# Processor.net
KiCad netlist of a schematic drawn in Altium Designer
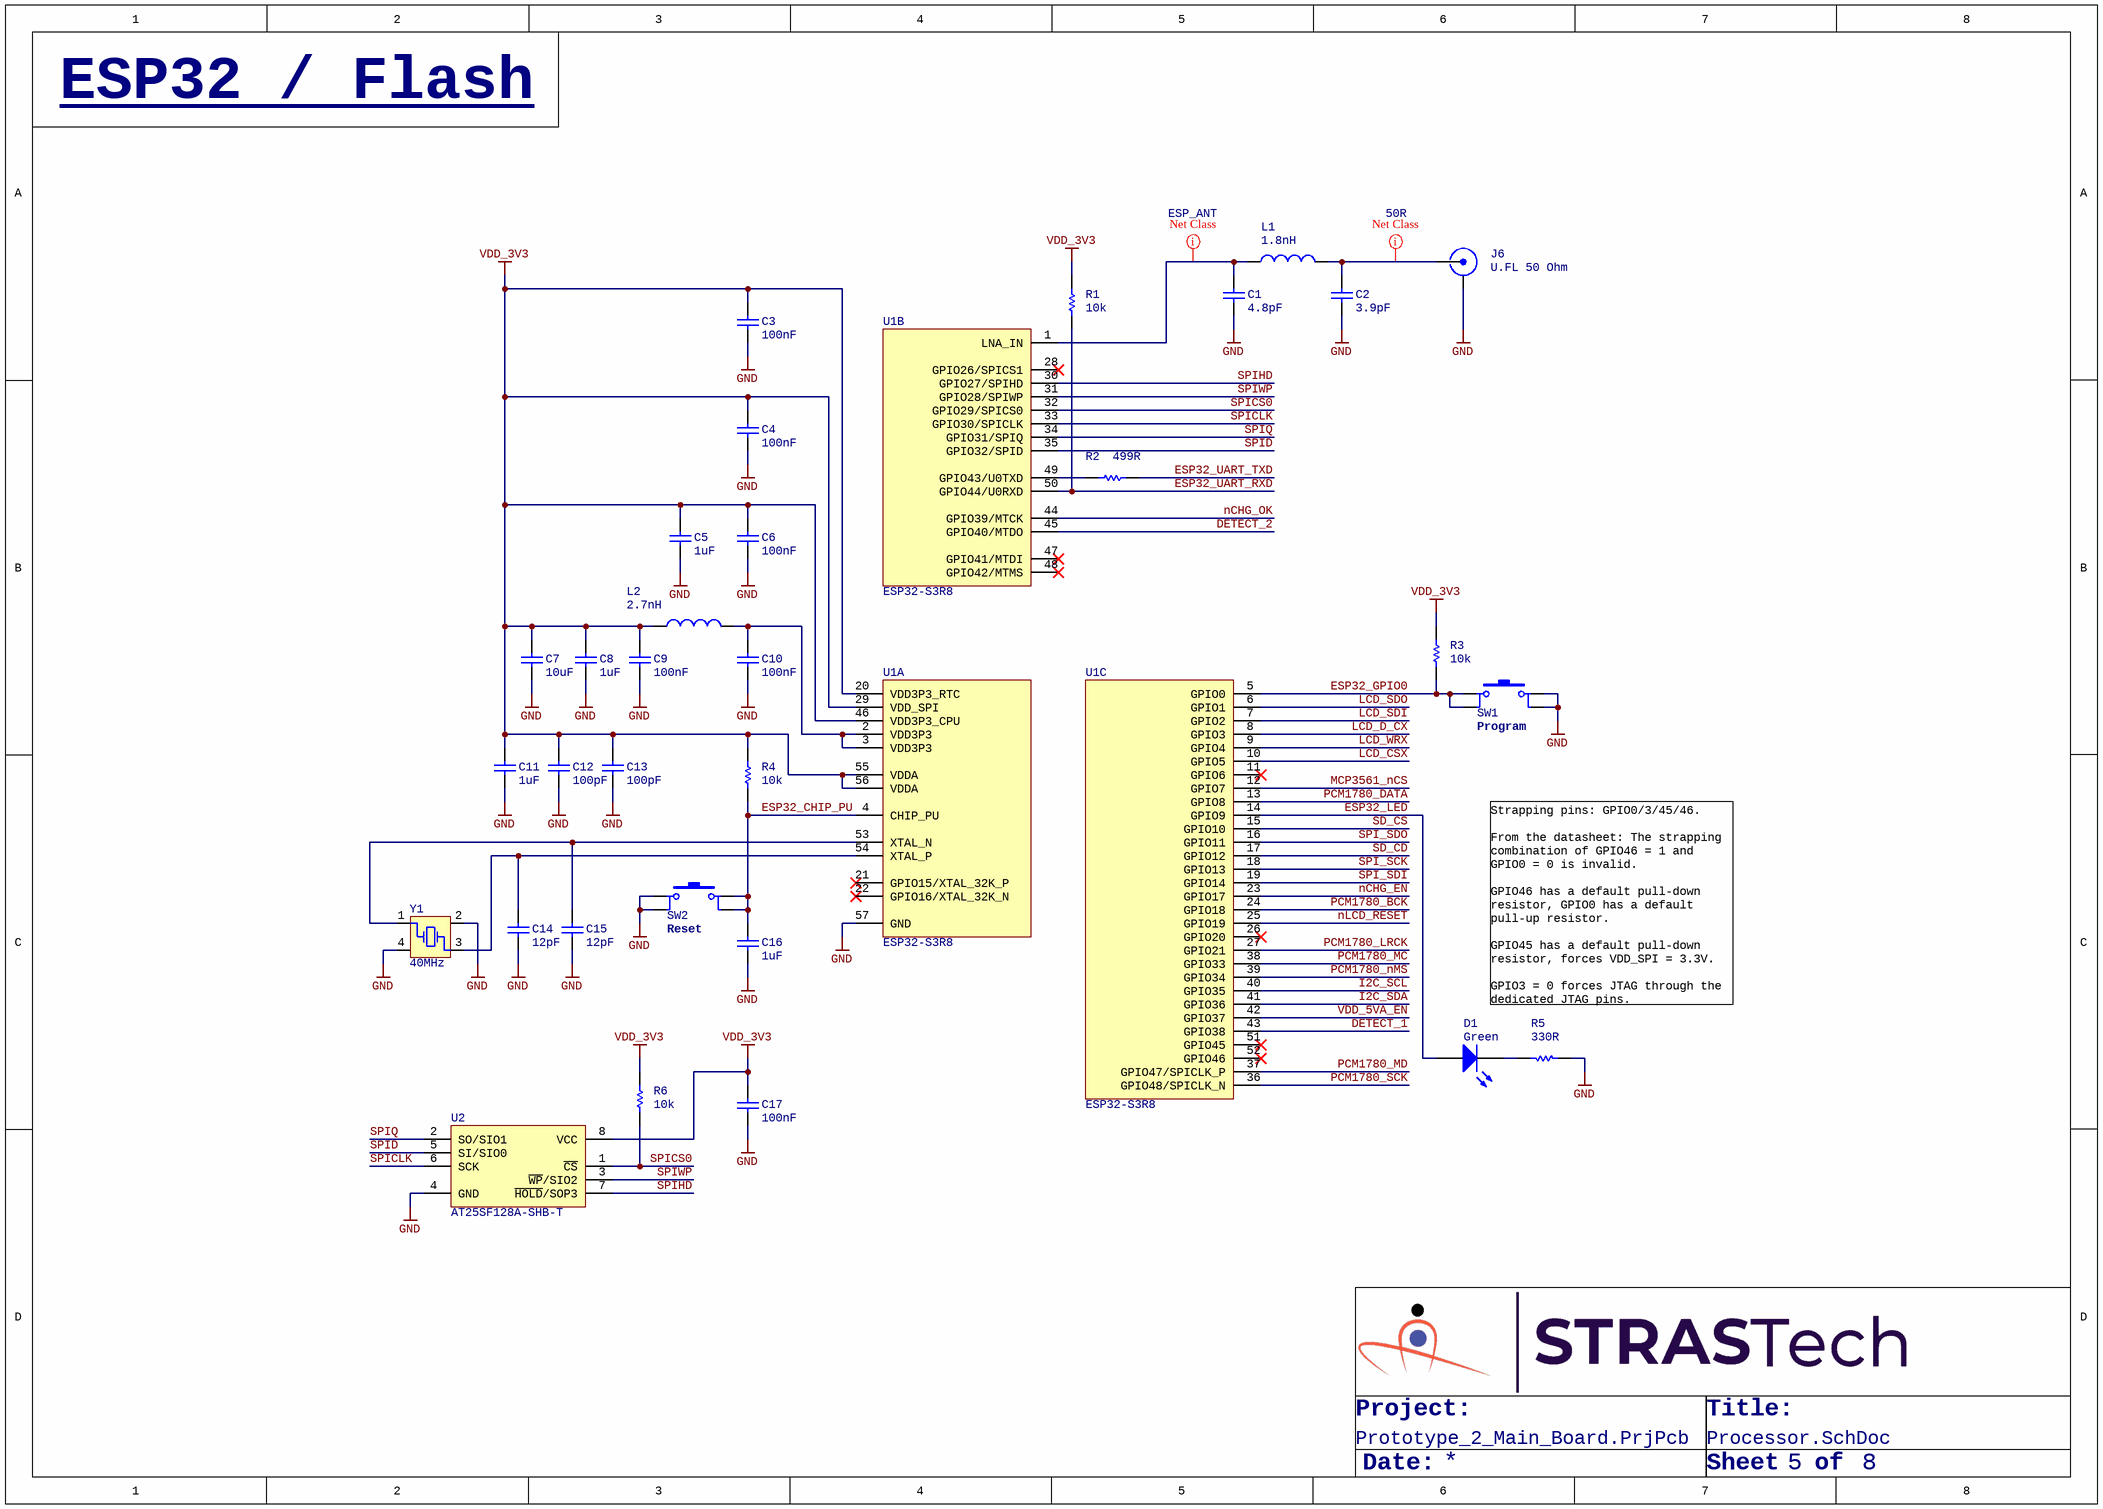
[diagram p0: Processor.SchDoc]

(export (version "E")
  (design (tool "Eeschema 10.0.6"))
  (components
    (comp (ref "C1")
      (value "4.8pF")
      (footprint "Cap,SMD,0402")
      (description "4.8 pF ±0.25pF 50V Ceramic Capacitor C0G, NP0 0402 (1005 Metric)")
      (fields
        (field (name "VENDOR PART NUMBER") "490-17481-1-ND")
        (field (name "MANUFACTURER") "Murata Electronics")
        (field (name "CREATEDBY") "Judd Foster")
      )
      (libsource (lib "symbols") (part "CAP,Cer,4.8pF,50VDC,C0G/NP0,0402"))
    )
    (comp (ref "C2")
      (value "3.9pF")
      (footprint "Cap,SMD,0402")
      (description "3.9 pF ±0.1pF 50V Ceramic Capacitor C0G, NP0 0402 (1005 Metric)")
      (fields
        (field (name "VENDOR PART NUMBER") "399-CBR04C399B5GACCT-ND")
        (field (name "MANUFACTURER") "KEMET")
        (field (name "CREATEDBY") "Judd Foster")
      )
      (libsource (lib "symbols") (part "CAP,Cer,3.9pF,50VDC,C0G/NP0,0402"))
    )
    (comp (ref "C3")
      (value "100nF")
      (footprint "Cap,SMD,0402")
      (description "0.1µF ±10% 25V Ceramic Capacitor X7R 0402 (1005 Metric)")
      (fields
        (field (name "VENDOR PART NUMBER") "490-14603-1-ND")
        (field (name "MANUFACTURER") "Murata Electronics")
        (field (name "CREATEDBY") "Judd Foster")
      )
      (libsource (lib "symbols") (part "CAP,Cer,100nF,25VDC,X7R,0402"))
    )
    (comp (ref "C4")
      (value "100nF")
      (footprint "Cap,SMD,0402")
      (description "0.1µF ±10% 25V Ceramic Capacitor X7R 0402 (1005 Metric)")
      (fields
        (field (name "VENDOR PART NUMBER") "490-14603-1-ND")
        (field (name "MANUFACTURER") "Murata Electronics")
        (field (name "CREATEDBY") "Judd Foster")
      )
      (libsource (lib "symbols") (part "CAP,Cer,100nF,25VDC,X7R,0402"))
    )
    (comp (ref "C5")
      (value "1uF")
      (footprint "Cap,SMD,0402")
      (description "1 µF ±10% 35V Ceramic Capacitor X5R 0402 (1005 Metric)")
      (fields
        (field (name "VENDOR PART NUMBER") "445-9073-1-ND")
        (field (name "MANUFACTURER") "TDK Corporation")
        (field (name "CREATEDBY") "Judd Foster")
      )
      (libsource (lib "symbols") (part "CAP,Cer,1uF,35VDC,X5R,0402"))
    )
    (comp (ref "C6")
      (value "100nF")
      (footprint "Cap,SMD,0402")
      (description "0.1µF ±10% 25V Ceramic Capacitor X7R 0402 (1005 Metric)")
      (fields
        (field (name "VENDOR PART NUMBER") "490-14603-1-ND")
        (field (name "MANUFACTURER") "Murata Electronics")
        (field (name "CREATEDBY") "Judd Foster")
      )
      (libsource (lib "symbols") (part "CAP,Cer,100nF,25VDC,X7R,0402"))
    )
    (comp (ref "C7")
      (value "10uF")
      (footprint "Cap,SMD,0402")
      (description "10 µF ±20% 10V Ceramic Capacitor X5R 0402 (1005 Metric)")
      (fields
        (field (name "VENDOR PART NUMBER") "1276-1450-1-ND")
        (field (name "MANUFACTURER") "Samsung Electro-Mechanics")
        (field (name "CREATEDBY") "Judd Foster")
      )
      (libsource (lib "symbols") (part "CAP,Cer,10uF,10VDC,X5R,0402"))
    )
    (comp (ref "C8")
      (value "1uF")
      (footprint "Cap,SMD,0402")
      (description "1 µF ±10% 35V Ceramic Capacitor X5R 0402 (1005 Metric)")
      (fields
        (field (name "VENDOR PART NUMBER") "445-9073-1-ND")
        (field (name "MANUFACTURER") "TDK Corporation")
        (field (name "CREATEDBY") "Judd Foster")
      )
      (libsource (lib "symbols") (part "CAP,Cer,1uF,35VDC,X5R,0402"))
    )
    (comp (ref "C9")
      (value "100nF")
      (footprint "Cap,SMD,0402")
      (description "0.1µF ±10% 25V Ceramic Capacitor X7R 0402 (1005 Metric)")
      (fields
        (field (name "VENDOR PART NUMBER") "490-14603-1-ND")
        (field (name "MANUFACTURER") "Murata Electronics")
        (field (name "CREATEDBY") "Judd Foster")
      )
      (libsource (lib "symbols") (part "CAP,Cer,100nF,25VDC,X7R,0402"))
    )
    (comp (ref "C10")
      (value "100nF")
      (footprint "Cap,SMD,0402")
      (description "0.1µF ±10% 25V Ceramic Capacitor X7R 0402 (1005 Metric)")
      (fields
        (field (name "VENDOR PART NUMBER") "490-14603-1-ND")
        (field (name "MANUFACTURER") "Murata Electronics")
        (field (name "CREATEDBY") "Judd Foster")
      )
      (libsource (lib "symbols") (part "CAP,Cer,100nF,25VDC,X7R,0402"))
    )
    (comp (ref "C11")
      (value "1uF")
      (footprint "Cap,SMD,0402")
      (description "1 µF ±10% 35V Ceramic Capacitor X5R 0402 (1005 Metric)")
      (fields
        (field (name "VENDOR PART NUMBER") "445-9073-1-ND")
        (field (name "MANUFACTURER") "TDK Corporation")
        (field (name "CREATEDBY") "Judd Foster")
      )
      (libsource (lib "symbols") (part "CAP,Cer,1uF,35VDC,X5R,0402"))
    )
    (comp (ref "C12")
      (value "100pF")
      (footprint "Cap,SMD,0402")
      (description "100pF ±5% 50V Ceramic Capacitor C0G, NP0 0402 (1005 Metric)")
      (fields
        (field (name "VENDOR PART NUMBER") "490-10669-1-ND")
        (field (name "MANUFACTURER") "Murata Electronics")
        (field (name "CREATEDBY") "Judd Foster")
      )
      (libsource (lib "symbols") (part "CAP,Cer,100pF,50VDC,C0G/NP0,0402"))
    )
    (comp (ref "C13")
      (value "100pF")
      (footprint "Cap,SMD,0402")
      (description "100pF ±5% 50V Ceramic Capacitor C0G, NP0 0402 (1005 Metric)")
      (fields
        (field (name "VENDOR PART NUMBER") "490-10669-1-ND")
        (field (name "MANUFACTURER") "Murata Electronics")
        (field (name "CREATEDBY") "Judd Foster")
      )
      (libsource (lib "symbols") (part "CAP,Cer,100pF,50VDC,C0G/NP0,0402"))
    )
    (comp (ref "C14")
      (value "12pF")
      (footprint "Cap,SMD,0402")
      (description "12pF ±5% 50V Ceramic Capacitor C0G, NP0 0402 (1005 Metric)")
      (fields
        (field (name "VENDOR PART NUMBER") "311-1016-1-ND")
        (field (name "MANUFACTURER") "Yageo")
        (field (name "CREATEDBY") "Judd Foster")
      )
      (libsource (lib "symbols") (part "CAP,Cer,12pF,50VDC,C0G/NP0,0402"))
    )
    (comp (ref "C15")
      (value "12pF")
      (footprint "Cap,SMD,0402")
      (description "12pF ±5% 50V Ceramic Capacitor C0G, NP0 0402 (1005 Metric)")
      (fields
        (field (name "VENDOR PART NUMBER") "311-1016-1-ND")
        (field (name "MANUFACTURER") "Yageo")
        (field (name "CREATEDBY") "Judd Foster")
      )
      (libsource (lib "symbols") (part "CAP,Cer,12pF,50VDC,C0G/NP0,0402"))
    )
    (comp (ref "C16")
      (value "1uF")
      (footprint "Cap,SMD,0402")
      (description "1µF ±20% 6.3V Ceramic Capacitor X5R 0402 (1005 Metric)")
      (fields
        (field (name "VENDOR PART NUMBER") "1276-1235-1-ND")
        (field (name "MANUFACTURER") "Samsung Electro-Mechanics")
        (field (name "CREATEDBY") "Judd Foster")
      )
      (libsource (lib "symbols") (part "CAP,Cer,1uF,6.3VDC,X5R,0402"))
    )
    (comp (ref "C17")
      (value "100nF")
      (footprint "Cap,SMD,0402")
      (description "0.1µF ±10% 25V Ceramic Capacitor X7R 0402 (1005 Metric)")
      (fields
        (field (name "VENDOR PART NUMBER") "490-14603-1-ND")
        (field (name "MANUFACTURER") "Murata Electronics")
        (field (name "CREATEDBY") "Judd Foster")
      )
      (libsource (lib "symbols") (part "CAP,Cer,100nF,25VDC,X7R,0402"))
    )
    (comp (ref "D1")
      (value "Green")
      (footprint "LED,0603")
      (description "Green 530nm LED Indication - Discrete 3V 0603 (1608 Metric)")
      (fields
        (field (name "MANUFACTURER") "Stanley Electric Co")
        (field (name "MANUFACTURER PART NUMBER") "THG1111C-0005-TR")
        (field (name "CREATEDBY") "Judd Foster")
      )
      (libsource (lib "symbols") (part "LED,Green,SMD,0603"))
    )
    (comp (ref "J6")
      (value "U.FL 50 Ohm")
      (footprint "CONN,UFL,50Ohm,SMD")
      (description "U.FL (UMCC) Connector Receptacle, Male Pin 50Ohm Surface Mount Solder")
      (fields
        (field (name "MANUFACTURER") "Hirose Electric Co Ltd")
        (field (name "MANUFACTURER PART NUMBER") "U.FL-R-SMT-1(40)")
        (field (name "CREATEDBY") "Judd Foster")
      )
      (libsource (lib "symbols") (part "Conn,RF,U.FL,50 Ohm,SMD"))
    )
    (comp (ref "L1")
      (value "1.8nH")
      (footprint "ind,0402")
      (description "1.8 nH Unshielded Multilayer Inductor 900 mA 100mOhm Max 0402 (1005 Metric)")
      (fields
        (field (name "VENDOR PART NUMBER") "490-1076-1-ND")
        (field (name "MANUFACTURER") "Murata Electronics")
        (field (name "CREATEDBY") "Judd Foster")
      )
      (libsource (lib "symbols") (part "IND,1.8nH,900mA,Multilayer,0402"))
    )
    (comp (ref "L2")
      (value "2.7nH")
      (footprint "ind,0402")
      (description "2.7nH Unshielded Multilayer Inductor 800mA 150mOhm Max 0402 (1005 Metric)")
      (fields
        (field (name "VENDOR PART NUMBER") "490-2615-1-ND")
        (field (name "MANUFACTURER") "Murata Electronics")
        (field (name "CREATEDBY") "Judd Foster")
      )
      (libsource (lib "symbols") (part "IND,2.7nH,800mA,Multilayer,0402"))
    )
    (comp (ref "R1")
      (value "10k")
      (footprint "RES,0402")
      (description "10 kOhms ±5% 0.063W, 1/16W Chip Resistor 0402 (1005 Metric) Automotive AEC-Q200 Thick Film")
      (fields
        (field (name "VENDOR PART NUMBER") "RMCF0402JT10K0CT-ND")
        (field (name "MANUFACTURER") "Stackpole Electronics Inc")
        (field (name "CREATEDBY") "Judd Foster")
      )
      (libsource (lib "symbols") (part "RES,10k,5%,0.063W,0402"))
    )
    (comp (ref "R2")
      (value "499R")
      (footprint "RES,0402")
      (description "499 Ohms ±1% 0.063W, 1/16W Chip Resistor 0402 (1005 Metric) Automotive AEC-Q200 Thick Film")
      (fields
        (field (name "MANUFACTURER") "Stackpole Electronics Inc")
        (field (name "MANUFACTURER PART NUMBER") "RMCF0402FT499R")
        (field (name "CREATEDBY") "Judd Foster")
      )
      (libsource (lib "symbols") (part "RES,499R,1%,0.063W,0402"))
    )
    (comp (ref "R3")
      (value "10k")
      (footprint "RES,0402")
      (description "10 kOhms ±5% 0.063W, 1/16W Chip Resistor 0402 (1005 Metric) Automotive AEC-Q200 Thick Film")
      (fields
        (field (name "VENDOR PART NUMBER") "RMCF0402JT10K0CT-ND")
        (field (name "MANUFACTURER") "Stackpole Electronics Inc")
        (field (name "CREATEDBY") "Judd Foster")
      )
      (libsource (lib "symbols") (part "RES,10k,5%,0.063W,0402"))
    )
    (comp (ref "R4")
      (value "10k")
      (footprint "RES,0402")
      (description "10 kOhms ±5% 0.063W, 1/16W Chip Resistor 0402 (1005 Metric) Automotive AEC-Q200 Thick Film")
      (fields
        (field (name "VENDOR PART NUMBER") "RMCF0402JT10K0CT-ND")
        (field (name "MANUFACTURER") "Stackpole Electronics Inc")
        (field (name "CREATEDBY") "Judd Foster")
      )
      (libsource (lib "symbols") (part "RES,10k,5%,0.063W,0402"))
    )
    (comp (ref "R5")
      (value "330R")
      (footprint "RES,0402")
      (description "330 Ohms ±5% 0.063W, 1/16W Chip Resistor 0402 (1005 Metric) Automotive AEC-Q200 Thick Film")
      (fields
        (field (name "MANUFACTURER") "Stackpole Electronics Inc")
        (field (name "MANUFACTURER PART NUMBER") "RMCF0402JT330R")
        (field (name "CREATEDBY") "Judd Foster")
      )
      (libsource (lib "symbols") (part "RES,330R,5%,0.063W,0402"))
    )
    (comp (ref "R6")
      (value "10k")
      (footprint "RES,0402")
      (description "10 kOhms ±5% 0.063W, 1/16W Chip Resistor 0402 (1005 Metric) Automotive AEC-Q200 Thick Film")
      (fields
        (field (name "VENDOR PART NUMBER") "RMCF0402JT10K0CT-ND")
        (field (name "MANUFACTURER") "Stackpole Electronics Inc")
        (field (name "CREATEDBY") "Judd Foster")
      )
      (libsource (lib "symbols") (part "RES,10k,5%,0.063W,0402"))
    )
    (comp (ref "SW1")
      (value "Switch")
      (footprint "Switch,Tactile,Micro,SPST-NO,SMD")
      (description "Tactile Switch SPST-NO Top Actuated Surface Mount")
      (fields
        (field (name "MANUFACTURER") "C&K")
        (field (name "MANUFACTURER PART NUMBER") "PTS525SM15SMTR2 LFS")
        (field (name "CREATEDBY") "Judd Foster")
      )
      (libsource (lib "symbols") (part "Switch,Tactile,SPST-NO,SMD,H1.5"))
    )
    (comp (ref "SW2")
      (value "Switch")
      (footprint "Switch,Tactile,Micro,SPST-NO,SMD")
      (description "Tactile Switch SPST-NO Top Actuated Surface Mount")
      (fields
        (field (name "MANUFACTURER") "C&K")
        (field (name "MANUFACTURER PART NUMBER") "PTS525SM15SMTR2 LFS")
        (field (name "CREATEDBY") "Judd Foster")
      )
      (libsource (lib "symbols") (part "Switch,Tactile,SPST-NO,SMD,H1.5"))
    )
    (comp (ref "U1")
      (value "ESP32-S3R8")
      (footprint "IC,QFN-56,7X7,P0.4MM")
      (fields
        (field (name "MANUFACTURER") "Espressif Systems")
        (field (name "VENDOR PART NUMBER") "1904-ESP32-S3R8-ND")
        (field (name "CREATEDBY") "Judd Foster")
      )
      (libsource (lib "") (part "ESP32-S3R8_1"))
    )
    (comp (ref "U2")
      (value "AT25SF128A-SHB-T")
      (footprint "IC,SOIC-8,1.27mm,W5.28")
      (description "FLASH - NOR Memory IC 128Mb (16M x 8) SPI - Quad I/O 133 MHz 8-SOIC")
      (fields
        (field (name "MANUFACTURER") "Adesto Technologies")
        (field (name "VENDOR PART NUMBER") "1265-1348-1-ND")
        (field (name "CREATEDBY") "Judd Foster")
      )
      (libsource (lib "symbols") (part "AT25SF128A-SHB-T"))
    )
    (comp (ref "Y1")
      (value "40MHz")
      (footprint "XTAL,SMD,4 Pin,2x2.5mm")
      (description "40 MHz ±7ppm Crystal 12pF 25 Ohms 4-SMD, No Lead")
      (fields
        (field (name "MANUFACTURER") "Hosonic Electronic Co., Ltd")
        (field (name "MANUFACTURER PART NUMBER") "E2SB40E000104E")
        (field (name "CREATEDBY") "Judd Foster")
      )
      (libsource (lib "symbols") (part "XTAL,40MHz,12pF,SMD"))
    )
  )
  (nets
    (net (code "1") (name "/DETECT_1") (class "Default")
      (node (ref "U1") (pin "43") (pinfunction "GPIO38_43") (pintype "passive"))
    )
    (net (code "2") (name "/DETECT_2") (class "Default")
      (node (ref "U1") (pin "45") (pinfunction "GPIO40/MTDO_45") (pintype "passive"))
    )
    (net (code "3") (name "/ESP32_CHIP_PU") (class "Default")
      (node (ref "C16") (pin "2") (pinfunction "2_2") (pintype "passive"))
      (node (ref "R4") (pin "2") (pinfunction "2_2") (pintype "passive"))
      (node (ref "SW2") (pin "3") (pinfunction "3_3") (pintype "passive"))
      (node (ref "SW2") (pin "4") (pinfunction "4_4") (pintype "passive"))
      (node (ref "U1") (pin "4") (pinfunction "CHIP_PU_4") (pintype "passive"))
    )
    (net (code "4") (name "/ESP32_GPIO0") (class "Default")
      (node (ref "R3") (pin "2") (pinfunction "2_2") (pintype "passive"))
      (node (ref "SW1") (pin "1") (pinfunction "1_1") (pintype "passive"))
      (node (ref "SW1") (pin "2") (pinfunction "2_2") (pintype "passive"))
      (node (ref "U1") (pin "5") (pinfunction "GPIO0_5") (pintype "passive"))
    )
    (net (code "5") (name "/ESP32_LED") (class "Default")
      (node (ref "D1") (pin "1") (pinfunction "A_1") (pintype "passive"))
      (node (ref "U1") (pin "14") (pinfunction "GPIO9_14") (pintype "passive"))
    )
    (net (code "6") (name "/ESP32_UART_RXD") (class "Default")
      (node (ref "R1") (pin "1") (pinfunction "1_1") (pintype "passive"))
      (node (ref "U1") (pin "50") (pinfunction "GPIO44/U0RXD_50") (pintype "passive"))
    )
    (net (code "7") (name "/ESP32_UART_TXD") (class "Default")
      (node (ref "R2") (pin "2") (pinfunction "2_2") (pintype "passive"))
    )
    (net (code "8") (name "/I2C_SCL") (class "Default")
      (node (ref "U1") (pin "40") (pinfunction "GPIO35_40") (pintype "passive"))
    )
    (net (code "9") (name "/I2C_SDA") (class "Default")
      (node (ref "U1") (pin "41") (pinfunction "GPIO36_41") (pintype "passive"))
    )
    (net (code "10") (name "/LCD_CSX") (class "Default")
      (node (ref "U1") (pin "10") (pinfunction "GPIO5_10") (pintype "passive"))
    )
    (net (code "11") (name "/LCD_D_CX") (class "Default")
      (node (ref "U1") (pin "8") (pinfunction "GPIO3_8") (pintype "passive"))
    )
    (net (code "12") (name "/LCD_SDI") (class "Default")
      (node (ref "U1") (pin "7") (pinfunction "GPIO2_7") (pintype "passive"))
    )
    (net (code "13") (name "/LCD_SDO") (class "Default")
      (node (ref "U1") (pin "6") (pinfunction "GPIO1_6") (pintype "passive"))
    )
    (net (code "14") (name "/LCD_WRX") (class "Default")
      (node (ref "U1") (pin "9") (pinfunction "GPIO4_9") (pintype "passive"))
    )
    (net (code "15") (name "/MCP3561_nCS") (class "Default")
      (node (ref "U1") (pin "12") (pinfunction "GPIO7_12") (pintype "passive"))
    )
    (net (code "16") (name "/PCM1780_BCK") (class "Default")
      (node (ref "U1") (pin "24") (pinfunction "GPIO18_24") (pintype "passive"))
    )
    (net (code "17") (name "/PCM1780_DATA") (class "Default")
      (node (ref "U1") (pin "13") (pinfunction "GPIO8_13") (pintype "passive"))
    )
    (net (code "18") (name "/PCM1780_LRCK") (class "Default")
      (node (ref "U1") (pin "27") (pinfunction "GPIO21_27") (pintype "passive"))
    )
    (net (code "19") (name "/PCM1780_MC") (class "Default")
      (node (ref "U1") (pin "38") (pinfunction "GPIO33_38") (pintype "passive"))
    )
    (net (code "20") (name "/PCM1780_MD") (class "Default")
      (node (ref "U1") (pin "37") (pinfunction "GPIO47/SPICLK_P_37") (pintype "passive"))
    )
    (net (code "21") (name "/PCM1780_SCK") (class "Default")
      (node (ref "U1") (pin "36") (pinfunction "GPIO48/SPICLK_N_36") (pintype "passive"))
    )
    (net (code "22") (name "/PCM1780_nMS") (class "Default")
      (node (ref "U1") (pin "39") (pinfunction "GPIO34_39") (pintype "passive"))
    )
    (net (code "23") (name "/SD_CD") (class "Default")
      (node (ref "U1") (pin "17") (pinfunction "GPIO12_17") (pintype "passive"))
    )
    (net (code "24") (name "/SD_CS") (class "Default")
      (node (ref "U1") (pin "15") (pinfunction "GPIO10_15") (pintype "passive"))
    )
    (net (code "25") (name "/SPICLK") (class "Default")
      (node (ref "U1") (pin "33") (pinfunction "GPIO30/SPICLK_33") (pintype "passive"))
      (node (ref "U2") (pin "6") (pinfunction "SCK_6") (pintype "passive"))
    )
    (net (code "26") (name "/SPICS0") (class "Default")
      (node (ref "R6") (pin "1") (pinfunction "1_1") (pintype "passive"))
      (node (ref "U1") (pin "32") (pinfunction "GPIO29/SPICS0_32") (pintype "passive"))
      (node (ref "U2") (pin "1") (pinfunction "~{CS}_1") (pintype "passive"))
    )
    (net (code "27") (name "/SPID") (class "Default")
      (node (ref "U1") (pin "35") (pinfunction "GPIO32/SPID_35") (pintype "passive"))
      (node (ref "U2") (pin "5") (pinfunction "SI/SIO0_5") (pintype "passive"))
    )
    (net (code "28") (name "/SPIHD") (class "Default")
      (node (ref "U1") (pin "30") (pinfunction "GPIO27/SPIHD_30") (pintype "passive"))
      (node (ref "U2") (pin "7") (pinfunction "~{HOLD}/SOP3_7") (pintype "passive"))
    )
    (net (code "29") (name "/SPIQ") (class "Default")
      (node (ref "U1") (pin "34") (pinfunction "GPIO31/SPIQ_34") (pintype "passive"))
      (node (ref "U2") (pin "2") (pinfunction "SO/SIO1_2") (pintype "passive"))
    )
    (net (code "30") (name "/SPIWP") (class "Default")
      (node (ref "U1") (pin "31") (pinfunction "GPIO28/SPIWP_31") (pintype "passive"))
      (node (ref "U2") (pin "3") (pinfunction "~{WP}/SIO2_3") (pintype "passive"))
    )
    (net (code "31") (name "/SPI_SCK") (class "Default")
      (node (ref "U1") (pin "18") (pinfunction "GPIO13_18") (pintype "passive"))
    )
    (net (code "32") (name "/SPI_SDI") (class "Default")
      (node (ref "U1") (pin "19") (pinfunction "GPIO14_19") (pintype "passive"))
    )
    (net (code "33") (name "/SPI_SDO") (class "Default")
      (node (ref "U1") (pin "16") (pinfunction "GPIO11_16") (pintype "passive"))
    )
    (net (code "34") (name "/VDD_5VA_EN") (class "Default")
      (node (ref "U1") (pin "42") (pinfunction "GPIO37_42") (pintype "passive"))
    )
    (net (code "35") (name "/nCHG_EN") (class "Default")
      (node (ref "U1") (pin "23") (pinfunction "GPIO17_23") (pintype "passive"))
    )
    (net (code "36") (name "/nCHG_OK") (class "Default")
      (node (ref "U1") (pin "44") (pinfunction "GPIO39/MTCK_44") (pintype "passive"))
    )
    (net (code "37") (name "/nLCD_RESET") (class "Default")
      (node (ref "U1") (pin "25") (pinfunction "GPIO19_25") (pintype "passive"))
    )
    (net (code "38") (name "GND") (class "Default")
      (node (ref "C1") (pin "1") (pinfunction "1_1") (pintype "passive"))
      (node (ref "C10") (pin "1") (pinfunction "1_1") (pintype "passive"))
      (node (ref "C11") (pin "1") (pinfunction "1_1") (pintype "passive"))
      (node (ref "C12") (pin "1") (pinfunction "1_1") (pintype "passive"))
      (node (ref "C13") (pin "1") (pinfunction "1_1") (pintype "passive"))
      (node (ref "C14") (pin "2") (pinfunction "2_2") (pintype "passive"))
      (node (ref "C15") (pin "2") (pinfunction "2_2") (pintype "passive"))
      (node (ref "C16") (pin "1") (pinfunction "1_1") (pintype "passive"))
      (node (ref "C17") (pin "1") (pinfunction "1_1") (pintype "passive"))
      (node (ref "C2") (pin "1") (pinfunction "1_1") (pintype "passive"))
      (node (ref "C3") (pin "1") (pinfunction "1_1") (pintype "passive"))
      (node (ref "C4") (pin "1") (pinfunction "1_1") (pintype "passive"))
      (node (ref "C5") (pin "1") (pinfunction "1_1") (pintype "passive"))
      (node (ref "C6") (pin "1") (pinfunction "1_1") (pintype "passive"))
      (node (ref "C7") (pin "1") (pinfunction "1_1") (pintype "passive"))
      (node (ref "C8") (pin "1") (pinfunction "1_1") (pintype "passive"))
      (node (ref "C9") (pin "1") (pinfunction "1_1") (pintype "passive"))
      (node (ref "J6") (pin "2") (pintype "passive"))
      (node (ref "R5") (pin "1") (pinfunction "1_1") (pintype "passive"))
      (node (ref "SW1") (pin "3") (pinfunction "3_3") (pintype "passive"))
      (node (ref "SW1") (pin "4") (pinfunction "4_4") (pintype "passive"))
      (node (ref "SW2") (pin "1") (pinfunction "1_1") (pintype "passive"))
      (node (ref "SW2") (pin "2") (pinfunction "2_2") (pintype "passive"))
      (node (ref "U1") (pin "57") (pinfunction "GND_57") (pintype "passive"))
      (node (ref "U2") (pin "4") (pinfunction "GND_4") (pintype "passive"))
      (node (ref "Y1") (pin "2") (pinfunction "GND_2") (pintype "passive"))
      (node (ref "Y1") (pin "4") (pinfunction "GND_4") (pintype "passive"))
    )
    (net (code "39") (name "Net-(C2-Pad2)") (class "Default")
      (node (ref "C2") (pin "2") (pinfunction "2_2") (pintype "passive"))
      (node (ref "J6") (pin "1") (pintype "passive"))
      (node (ref "L1") (pin "2") (pinfunction "2_2") (pintype "passive"))
    )
    (net (code "40") (name "Net-(C10-Pad2)") (class "Default")
      (node (ref "C10") (pin "2") (pinfunction "2_2") (pintype "passive"))
      (node (ref "L2") (pin "2") (pinfunction "2_2") (pintype "passive"))
      (node (ref "U1") (pin "2") (pinfunction "VDD3P3_2") (pintype "passive"))
      (node (ref "U1") (pin "3") (pinfunction "VDD3P3_3") (pintype "passive"))
    )
    (net (code "41") (name "Net-(D1-K)") (class "Default")
      (node (ref "D1") (pin "2") (pinfunction "K_2") (pintype "passive"))
      (node (ref "R5") (pin "2") (pinfunction "2_2") (pintype "passive"))
    )
    (net (code "42") (name "Net-(U1A-XTAL_N)") (class "Default")
      (node (ref "C15") (pin "1") (pinfunction "1_1") (pintype "passive"))
      (node (ref "U1") (pin "53") (pinfunction "XTAL_N_53") (pintype "passive"))
      (node (ref "Y1") (pin "1") (pinfunction "OSC1_1") (pintype "passive"))
    )
    (net (code "43") (name "Net-(U1A-XTAL_P)") (class "Default")
      (node (ref "C14") (pin "1") (pinfunction "1_1") (pintype "passive"))
      (node (ref "U1") (pin "54") (pinfunction "XTAL_P_54") (pintype "passive"))
      (node (ref "Y1") (pin "3") (pinfunction "OSC2_3") (pintype "passive"))
    )
    (net (code "44") (name "Net-(U1B-GPIO43{slash}U0TXD)") (class "Default")
      (node (ref "R2") (pin "1") (pinfunction "1_1") (pintype "passive"))
      (node (ref "U1") (pin "49") (pinfunction "GPIO43/U0TXD_49") (pintype "passive"))
    )
    (net (code "45") (name "Net-(U1B-LNA_IN)") (class "Default")
      (node (ref "C1") (pin "2") (pinfunction "2_2") (pintype "passive"))
      (node (ref "L1") (pin "1") (pinfunction "1_1") (pintype "passive"))
      (node (ref "U1") (pin "1") (pinfunction "LNA_IN_1") (pintype "passive"))
    )
    (net (code "46") (name "VDD_3V3") (class "Default")
      (node (ref "C11") (pin "2") (pinfunction "2_2") (pintype "passive"))
      (node (ref "C12") (pin "2") (pinfunction "2_2") (pintype "passive"))
      (node (ref "C13") (pin "2") (pinfunction "2_2") (pintype "passive"))
      (node (ref "C17") (pin "2") (pinfunction "2_2") (pintype "passive"))
      (node (ref "C3") (pin "2") (pinfunction "2_2") (pintype "passive"))
      (node (ref "C4") (pin "2") (pinfunction "2_2") (pintype "passive"))
      (node (ref "C5") (pin "2") (pinfunction "2_2") (pintype "passive"))
      (node (ref "C6") (pin "2") (pinfunction "2_2") (pintype "passive"))
      (node (ref "C7") (pin "2") (pinfunction "2_2") (pintype "passive"))
      (node (ref "C8") (pin "2") (pinfunction "2_2") (pintype "passive"))
      (node (ref "C9") (pin "2") (pinfunction "2_2") (pintype "passive"))
      (node (ref "L2") (pin "1") (pinfunction "1_1") (pintype "passive"))
      (node (ref "R1") (pin "2") (pinfunction "2_2") (pintype "passive"))
      (node (ref "R3") (pin "1") (pinfunction "1_1") (pintype "passive"))
      (node (ref "R4") (pin "1") (pinfunction "1_1") (pintype "passive"))
      (node (ref "R6") (pin "2") (pinfunction "2_2") (pintype "passive"))
      (node (ref "U1") (pin "20") (pinfunction "VDD3P3_RTC_20") (pintype "passive"))
      (node (ref "U1") (pin "29") (pinfunction "VDD_SPI_29") (pintype "passive"))
      (node (ref "U1") (pin "46") (pinfunction "VDD3P3_CPU_46") (pintype "passive"))
      (node (ref "U1") (pin "55") (pinfunction "VDDA_55") (pintype "passive"))
      (node (ref "U1") (pin "56") (pinfunction "VDDA_56") (pintype "passive"))
      (node (ref "U2") (pin "8") (pinfunction "VCC_8") (pintype "passive"))
    )
    (net (code "47") (name "unconnected-(U1A-GPIO15{slash}XTAL_32K_P-Pad21)") (class "Default")
      (node (ref "U1") (pin "21") (pinfunction "GPIO15/XTAL_32K_P_21") (pintype "passive+no_connect"))
    )
    (net (code "48") (name "unconnected-(U1A-GPIO16{slash}XTAL_32K_N-Pad22)") (class "Default")
      (node (ref "U1") (pin "22") (pinfunction "GPIO16/XTAL_32K_N_22") (pintype "passive+no_connect"))
    )
    (net (code "49") (name "unconnected-(U1B-GPIO26{slash}SPICS1-Pad28)") (class "Default")
      (node (ref "U1") (pin "28") (pinfunction "GPIO26/SPICS1_28") (pintype "passive+no_connect"))
    )
    (net (code "50") (name "unconnected-(U1B-GPIO41{slash}MTDI-Pad47)") (class "Default")
      (node (ref "U1") (pin "47") (pinfunction "GPIO41/MTDI_47") (pintype "passive+no_connect"))
    )
    (net (code "51") (name "unconnected-(U1B-GPIO42{slash}MTMS-Pad48)") (class "Default")
      (node (ref "U1") (pin "48") (pinfunction "GPIO42/MTMS_48") (pintype "passive+no_connect"))
    )
    (net (code "52") (name "unconnected-(U1C-GPIO6-Pad11)") (class "Default")
      (node (ref "U1") (pin "11") (pinfunction "GPIO6_11") (pintype "passive+no_connect"))
    )
    (net (code "53") (name "unconnected-(U1C-GPIO20-Pad26)") (class "Default")
      (node (ref "U1") (pin "26") (pinfunction "GPIO20_26") (pintype "passive+no_connect"))
    )
    (net (code "54") (name "unconnected-(U1C-GPIO45-Pad51)") (class "Default")
      (node (ref "U1") (pin "51") (pinfunction "GPIO45_51") (pintype "passive+no_connect"))
    )
    (net (code "55") (name "unconnected-(U1C-GPIO46-Pad52)") (class "Default")
      (node (ref "U1") (pin "52") (pinfunction "GPIO46_52") (pintype "passive+no_connect"))
    )
  )
)
